# pulser.net
KiCad netlist of a schematic drawn in Altium Designer
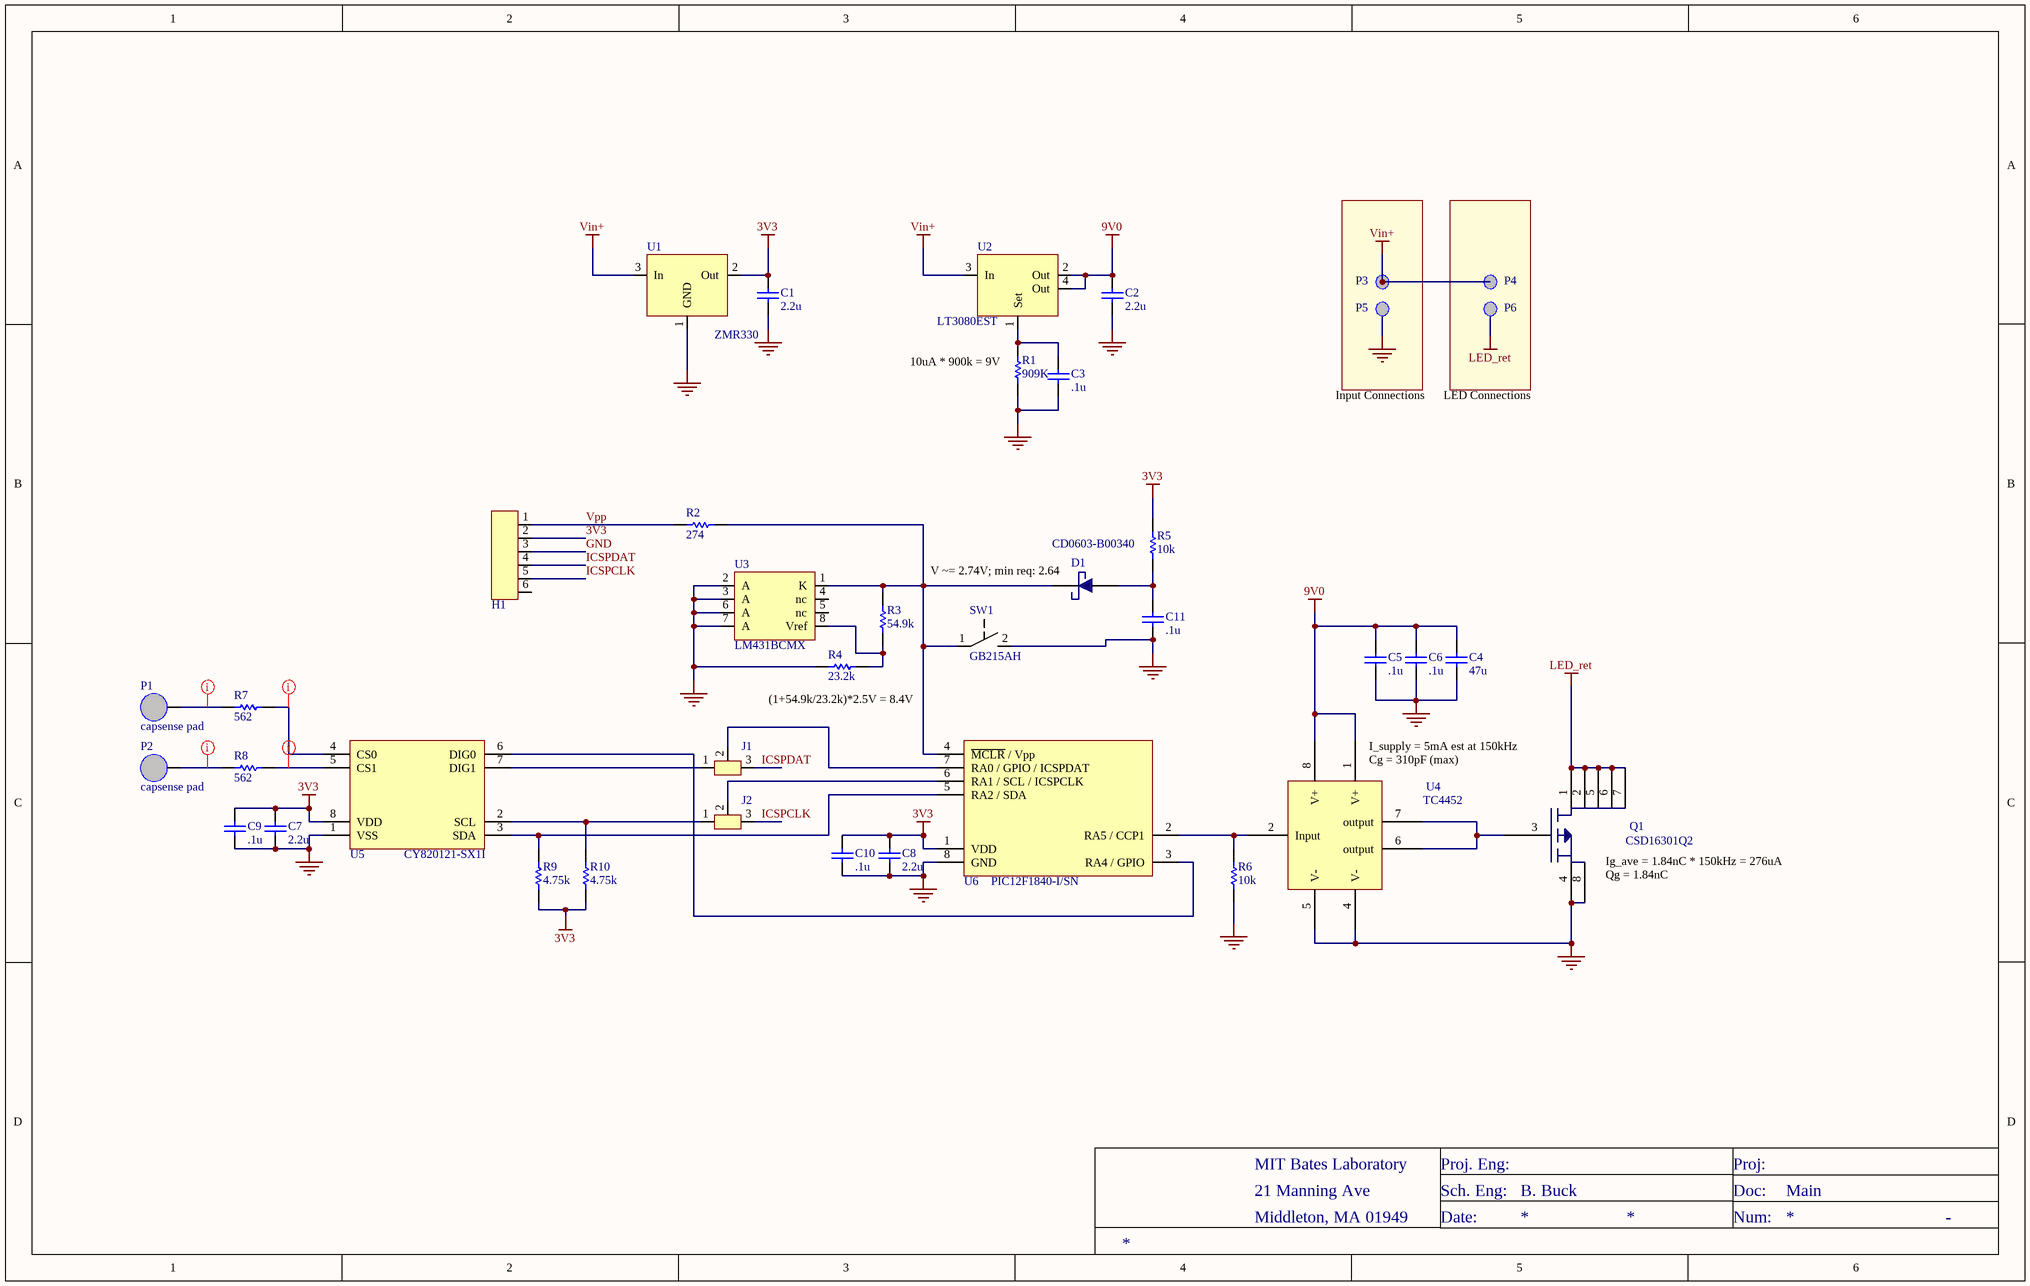
[diagram p0: pulser.SchDoc]

(export (version "E")
  (design (tool "Eeschema 10.0.6"))
  (components
    (comp (ref "C1")
      (value "2.2u")
      (footprint "SMD1210")
      (description "Capacitor")
      (fields (field (name "PARTNUMBER") "C1210C225K5RAC") (field (name "MANUFACTURER") "Kemet"))
      (libsource (lib "pulser") (part "Cap"))
    )
    (comp (ref "C2")
      (value "2.2u")
      (footprint "SMD1210")
      (description "Capacitor")
      (fields (field (name "PARTNUMBER") "C1210C225K5RAC") (field (name "MANUFACTURER") "Kemet"))
      (libsource (lib "pulser") (part "Cap"))
    )
    (comp (ref "C3")
      (value ".1u")
      (footprint "SMD0603")
      (description "Capacitor")
      (fields
        (field (name "PARTNUMBER") "250R14W104KV4T")
        (field (name "MANUFACTURER") "Johanson Dielectrics")
      )
      (libsource (lib "pulser") (part "Cap"))
    )
    (comp (ref "C4")
      (value "47u")
      (footprint "SMD1812")
      (description "Capacitor")
      (fields (field (name "PARTNUMBER") "C1812C475K5RAC") (field (name "MANUFACTURER") "Kemet"))
      (libsource (lib "pulser") (part "Cap"))
    )
    (comp (ref "C5")
      (value ".1u")
      (footprint "SMD0603")
      (description "Capacitor")
      (fields
        (field (name "PARTNUMBER") "250R14W104KV4T")
        (field (name "MANUFACTURER") "Johanson Dielectrics")
      )
      (libsource (lib "pulser") (part "Cap"))
    )
    (comp (ref "C6")
      (value ".1u")
      (footprint "SMD0603")
      (description "Capacitor")
      (fields
        (field (name "PARTNUMBER") "250R14W104KV4T")
        (field (name "MANUFACTURER") "Johanson Dielectrics")
      )
      (libsource (lib "pulser") (part "Cap"))
    )
    (comp (ref "C7")
      (value "2.2u")
      (footprint "SMD1210")
      (description "Capacitor")
      (fields (field (name "PARTNUMBER") "C1210C225K5RAC") (field (name "MANUFACTURER") "Kemet"))
      (libsource (lib "pulser") (part "Cap"))
    )
    (comp (ref "C8")
      (value "2.2u")
      (footprint "SMD1210")
      (description "Capacitor")
      (fields (field (name "PARTNUMBER") "C1210C225K5RAC") (field (name "MANUFACTURER") "Kemet"))
      (libsource (lib "pulser") (part "Cap"))
    )
    (comp (ref "C9")
      (value ".1u")
      (footprint "SMD0603")
      (description "Capacitor")
      (fields
        (field (name "PARTNUMBER") "250R14W104KV4T")
        (field (name "MANUFACTURER") "Johanson Dielectrics")
      )
      (libsource (lib "pulser") (part "Cap"))
    )
    (comp (ref "C10")
      (value ".1u")
      (footprint "SMD0603")
      (description "Capacitor")
      (fields
        (field (name "PARTNUMBER") "250R14W104KV4T")
        (field (name "MANUFACTURER") "Johanson Dielectrics")
      )
      (libsource (lib "pulser") (part "Cap"))
    )
    (comp (ref "C11")
      (value ".1u")
      (footprint "SMD0603")
      (description "Capacitor")
      (fields
        (field (name "PARTNUMBER") "250R14W104KV4T")
        (field (name "MANUFACTURER") "Johanson Dielectrics")
      )
      (libsource (lib "pulser") (part "Cap"))
    )
    (comp (ref "D1")
      (value "CD0603-B00340")
      (footprint "SMD0603 Polarized")
      (description "Schottky Diode")
      (fields (field (name "MANUFACTURER") "Bourns"))
      (libsource (lib "pulser") (part "CD0603-B00340"))
    )
    (comp (ref "H1")
      (value "6 pin header")
      (footprint "6 pin header")
      (description "6 Pin Header")
      (libsource (lib "pulser") (part "6 pin header"))
    )
    (comp (ref "J1")
      (value "jumper")
      (footprint "3 PIN HEADER")
      (description "Three Pin Jumper")
      (libsource (lib "pulser") (part "jumper"))
    )
    (comp (ref "J2")
      (value "jumper")
      (footprint "3 PIN HEADER")
      (description "Three Pin Jumper")
      (libsource (lib "pulser") (part "jumper"))
    )
    (comp (ref "P1")
      (value "capsense pad")
      (footprint "capsense 1cm")
      (description "circular capsense pad")
      (libsource (lib "pulser") (part "capsense pad 1"))
    )
    (comp (ref "P2")
      (value "capsense pad")
      (footprint "capsense 1cm")
      (description "circular capsense pad")
      (libsource (lib "pulser") (part "capsense pad 1"))
    )
    (comp (ref "P3")
      (value "16AWG Solder Point")
      (footprint "16 AWG Solder Point")
      (libsource (lib "pulser") (part "16AWG Solder Point"))
    )
    (comp (ref "P4")
      (value "16AWG Solder Point")
      (footprint "16 AWG Solder Point")
      (libsource (lib "pulser") (part "16AWG Solder Point"))
    )
    (comp (ref "P5")
      (value "16AWG Solder Point")
      (footprint "16 AWG Solder Point")
      (libsource (lib "pulser") (part "16AWG Solder Point"))
    )
    (comp (ref "P6")
      (value "16AWG Solder Point")
      (footprint "16 AWG Solder Point")
      (libsource (lib "pulser") (part "16AWG Solder Point"))
    )
    (comp (ref "Q1")
      (value "CSD16301Q2")
      (footprint "CSD16301Q2")
      (description "N Ch. MOSFET")
      (fields (field (name "MANUFACTURER") "Texas Instruments"))
      (libsource (lib "pulser") (part "CSD16301Q2"))
    )
    (comp (ref "R1")
      (value "909K")
      (footprint "SMD0603")
      (description "Resistor")
      (fields (field (name "PARTNUMBER") "CRCW0603909KFK") (field (name "MANUFACTURER") "Vishay / Dale"))
      (libsource (lib "pulser") (part "Res"))
    )
    (comp (ref "R2")
      (value "274")
      (footprint "SMD0603")
      (description "Resistor")
      (fields (field (name "PARTNUMBER") "CRCW0603274RFK") (field (name "MANUFACTURER") "Vishay / Dale"))
      (libsource (lib "pulser") (part "Res"))
    )
    (comp (ref "R3")
      (value "54.9k")
      (footprint "SMD0603")
      (description "Resistor")
      (fields (field (name "PARTNUMBER") "CRCW060354K9FK") (field (name "MANUFACTURER") "Vishay / Dale"))
      (libsource (lib "pulser") (part "Res"))
    )
    (comp (ref "R4")
      (value "23.2k")
      (footprint "SMD0603")
      (description "Resistor")
      (fields (field (name "PARTNUMBER") "CRCW060323K2FK") (field (name "MANUFACTURER") "Vishay / Dale"))
      (libsource (lib "pulser") (part "Res"))
    )
    (comp (ref "R5")
      (value "10k")
      (footprint "SMD0603")
      (description "Resistor")
      (fields (field (name "PARTNUMBER") "CRCW060310K0FK") (field (name "MANUFACTURER") "Vishay / Dale"))
      (libsource (lib "pulser") (part "Res"))
    )
    (comp (ref "R6")
      (value "10k")
      (footprint "SMD0603")
      (description "Resistor")
      (fields (field (name "PARTNUMBER") "CRCW060310K0FK") (field (name "MANUFACTURER") "Vishay / Dale"))
      (libsource (lib "pulser") (part "Res"))
    )
    (comp (ref "R7")
      (value "562")
      (footprint "SMD0603")
      (description "Resistor")
      (fields (field (name "PARTNUMBER") "CRCW0603562RFK") (field (name "MANUFACTURER") "Vishay / Dale"))
      (libsource (lib "pulser") (part "Res"))
    )
    (comp (ref "R8")
      (value "562")
      (footprint "SMD0603")
      (description "Resistor")
      (fields (field (name "PARTNUMBER") "CRCW0603562RFK") (field (name "MANUFACTURER") "Vishay / Dale"))
      (libsource (lib "pulser") (part "Res"))
    )
    (comp (ref "R9")
      (value "4.75k")
      (footprint "SMD0603")
      (description "Resistor")
      (fields (field (name "PARTNUMBER") "CRCW06034K75FK") (field (name "MANUFACTURER") "Vishay / Dale"))
      (libsource (lib "pulser") (part "Res"))
    )
    (comp (ref "R10")
      (value "4.75k")
      (footprint "SMD0603")
      (description "Resistor")
      (fields (field (name "PARTNUMBER") "CRCW06034K75FK") (field (name "MANUFACTURER") "Vishay / Dale"))
      (libsource (lib "pulser") (part "Res"))
    )
    (comp (ref "SW1")
      (value "GB215AH")
      (footprint "GB215AH")
      (description "SPST Normally Open Switch")
      (fields (field (name "PARTNUMBER") "GB125AH") (field (name "MANUFACTURER") "NKK Switches"))
      (libsource (lib "pulser") (part "GB215AH"))
    )
    (comp (ref "U1")
      (value "ZMR330")
      (footprint "SOT23 - Diodes")
      (description "Diodes 3.3V LDO regulator, 50mA")
      (fields (field (name "MANUFACTURER") "Diodes") (field (name "PARTNUMBER") "ZMR330FTA"))
      (libsource (lib "pulser") (part "ZMR330"))
    )
    (comp (ref "U2")
      (value "LT3080EST")
      (footprint "SOT233")
      (description "Adjustable Regulator, SOT-223 Package")
      (fields (field (name "MANUFACTURER") "Linear Technologies"))
      (libsource (lib "pulser") (part "LT3080EST"))
    )
    (comp (ref "U3")
      (value "LM431BCMX")
      (footprint "8 PIN SOIC")
      (description "Adjustable Voltage Reference")
      (fields (field (name "MANUFACTURER") "Fairchild Semiconductor") (field (name "PARTNUMBER") "LM431ACMX"))
      (libsource (lib "pulser") (part "LM431BCMX"))
    )
    (comp (ref "U4")
      (value "TC4452")
      (footprint "8 PIN SOIC")
      (description "MOSFET Gate Driver, Low Side, Non Inverting 13A max")
      (fields (field (name "MANUFACTURER") "Microchip") (field (name "PARTNUMBER") "TC4452VOA"))
      (libsource (lib "pulser") (part "TC4452"))
    )
    (comp (ref "U5")
      (value "CY820121-SX1I")
      (footprint "8 PIN SOIC")
      (description "Capsense Module, 2 button")
      (fields (field (name "PARTNUMBER") "CY8C20121-SX1IX") (field (name "MANUFACTURER") "Cypress"))
      (libsource (lib "pulser") (part "CY820121-SX1I"))
    )
    (comp (ref "U6")
      (value "PIC12F1840-I/SN")
      (footprint "8 PIN SOIC")
      (description "8 Bit RISC uController")
      (fields (field (name "MANUFACTURER") "Microchip"))
      (libsource (lib "pulser") (part "PIC12F1840-I/SN"))
    )
  )
  (nets
    (net (code "1") (name "/ICSPCLK") (class "Default")
      (node (ref "H1") (pin "5") (pinfunction "5_5") (pintype "passive"))
      (node (ref "J2") (pin "3") (pinfunction "3_3") (pintype "passive"))
    )
    (net (code "2") (name "/ICSPDAT") (class "Default")
      (node (ref "H1") (pin "4") (pinfunction "4_4") (pintype "passive"))
      (node (ref "J1") (pin "3") (pinfunction "3_3") (pintype "passive"))
    )
    (net (code "3") (name "/Vpp") (class "Default")
      (node (ref "H1") (pin "1") (pinfunction "1_1") (pintype "passive"))
      (node (ref "R2") (pin "2") (pinfunction "2_2") (pintype "passive"))
    )
    (net (code "4") (name "3V3") (class "Default")
      (node (ref "C1") (pin "2") (pinfunction "2_2") (pintype "passive"))
      (node (ref "C10") (pin "2") (pinfunction "2_2") (pintype "passive"))
      (node (ref "C7") (pin "2") (pinfunction "2_2") (pintype "passive"))
      (node (ref "C8") (pin "2") (pinfunction "2_2") (pintype "passive"))
      (node (ref "C9") (pin "2") (pinfunction "2_2") (pintype "passive"))
      (node (ref "H1") (pin "2") (pinfunction "2_2") (pintype "passive"))
      (node (ref "R10") (pin "2") (pinfunction "2_2") (pintype "passive"))
      (node (ref "R5") (pin "1") (pinfunction "1_1") (pintype "passive"))
      (node (ref "R9") (pin "2") (pinfunction "2_2") (pintype "passive"))
      (node (ref "U1") (pin "2") (pinfunction "Out_2") (pintype "passive"))
      (node (ref "U5") (pin "8") (pinfunction "VDD_8") (pintype "passive"))
      (node (ref "U6") (pin "1") (pinfunction "VDD_1") (pintype "passive"))
    )
    (net (code "5") (name "9V0") (class "Default")
      (node (ref "C2") (pin "2") (pinfunction "2_2") (pintype "passive"))
      (node (ref "C4") (pin "2") (pinfunction "2_2") (pintype "passive"))
      (node (ref "C5") (pin "2") (pinfunction "2_2") (pintype "passive"))
      (node (ref "C6") (pin "2") (pinfunction "2_2") (pintype "passive"))
      (node (ref "U2") (pin "2") (pinfunction "Out_2") (pintype "passive"))
      (node (ref "U2") (pin "4") (pinfunction "Out_4") (pintype "passive"))
      (node (ref "U4") (pin "1") (pinfunction "V+_1") (pintype "passive"))
      (node (ref "U4") (pin "8") (pinfunction "V+_8") (pintype "passive"))
    )
    (net (code "6") (name "GND") (class "Default")
      (node (ref "C1") (pin "1") (pinfunction "1_1") (pintype "passive"))
      (node (ref "C10") (pin "1") (pinfunction "1_1") (pintype "passive"))
      (node (ref "C11") (pin "1") (pinfunction "1_1") (pintype "passive"))
      (node (ref "C2") (pin "1") (pinfunction "1_1") (pintype "passive"))
      (node (ref "C3") (pin "1") (pinfunction "1_1") (pintype "passive"))
      (node (ref "C4") (pin "1") (pinfunction "1_1") (pintype "passive"))
      (node (ref "C5") (pin "1") (pinfunction "1_1") (pintype "passive"))
      (node (ref "C6") (pin "1") (pinfunction "1_1") (pintype "passive"))
      (node (ref "C7") (pin "1") (pinfunction "1_1") (pintype "passive"))
      (node (ref "C8") (pin "1") (pinfunction "1_1") (pintype "passive"))
      (node (ref "C9") (pin "1") (pinfunction "1_1") (pintype "passive"))
      (node (ref "H1") (pin "3") (pinfunction "3_3") (pintype "passive"))
      (node (ref "P5") (pin "1") (pinfunction "1_1") (pintype "passive"))
      (node (ref "Q1") (pin "4") (pintype "passive"))
      (node (ref "Q1") (pin "8") (pintype "passive"))
      (node (ref "R1") (pin "1") (pinfunction "1_1") (pintype "passive"))
      (node (ref "R4") (pin "2") (pinfunction "2_2") (pintype "passive"))
      (node (ref "R6") (pin "2") (pinfunction "2_2") (pintype "passive"))
      (node (ref "SW1") (pin "2") (pinfunction "2_2") (pintype "passive"))
      (node (ref "U1") (pin "1") (pinfunction "GND_1") (pintype "passive"))
      (node (ref "U3") (pin "2") (pinfunction "A_2") (pintype "passive"))
      (node (ref "U3") (pin "3") (pinfunction "A_3") (pintype "passive"))
      (node (ref "U3") (pin "6") (pinfunction "A_6") (pintype "passive"))
      (node (ref "U3") (pin "7") (pinfunction "A_7") (pintype "passive"))
      (node (ref "U4") (pin "4") (pinfunction "V-_4") (pintype "passive"))
      (node (ref "U4") (pin "5") (pinfunction "V-_5") (pintype "passive"))
      (node (ref "U5") (pin "1") (pinfunction "VSS_1") (pintype "passive"))
      (node (ref "U6") (pin "8") (pinfunction "GND_8") (pintype "passive"))
    )
    (net (code "7") (name "LED_ret") (class "Default")
      (node (ref "P6") (pin "1") (pinfunction "1_1") (pintype "passive"))
      (node (ref "Q1") (pin "1") (pintype "passive"))
      (node (ref "Q1") (pin "2") (pintype "passive"))
      (node (ref "Q1") (pin "5") (pintype "passive"))
      (node (ref "Q1") (pin "6") (pintype "passive"))
      (node (ref "Q1") (pin "7") (pintype "passive"))
    )
    (net (code "8") (name "Net-(D1-A)") (class "Default")
      (node (ref "C11") (pin "2") (pinfunction "2_2") (pintype "passive"))
      (node (ref "D1") (pin "2") (pinfunction "A_2") (pintype "passive"))
      (node (ref "R5") (pin "2") (pinfunction "2_2") (pintype "passive"))
    )
    (net (code "9") (name "Net-(D1-K)") (class "Default")
      (node (ref "D1") (pin "1") (pinfunction "K_1") (pintype "passive"))
      (node (ref "R2") (pin "1") (pinfunction "1_1") (pintype "passive"))
      (node (ref "R3") (pin "2") (pinfunction "2_2") (pintype "passive"))
      (node (ref "SW1") (pin "1") (pinfunction "1_1") (pintype "passive"))
      (node (ref "U3") (pin "1") (pinfunction "K_1") (pintype "passive"))
      (node (ref "U6") (pin "4") (pinfunction "~{MCLR}_/_Vpp_4") (pintype "passive"))
    )
    (net (code "10") (name "Net-(P1-Pad1)") (class "Default")
      (node (ref "P1") (pin "1") (pintype "passive"))
      (node (ref "R7") (pin "2") (pinfunction "2_2") (pintype "passive"))
    )
    (net (code "11") (name "Net-(P2-Pad1)") (class "Default")
      (node (ref "P2") (pin "1") (pintype "passive"))
      (node (ref "R8") (pin "2") (pinfunction "2_2") (pintype "passive"))
    )
    (net (code "12") (name "Net-(Q1-Pad3)") (class "Default")
      (node (ref "Q1") (pin "3") (pintype "passive"))
      (node (ref "U4") (pin "6") (pinfunction "output_6") (pintype "passive"))
      (node (ref "U4") (pin "7") (pinfunction "output_7") (pintype "passive"))
    )
    (net (code "13") (name "Net-(U2-Set)") (class "Default")
      (node (ref "C3") (pin "2") (pinfunction "2_2") (pintype "passive"))
      (node (ref "R1") (pin "2") (pinfunction "2_2") (pintype "passive"))
      (node (ref "U2") (pin "1") (pinfunction "Set_1") (pintype "passive"))
    )
    (net (code "14") (name "Net-(U3-Vref)") (class "Default")
      (node (ref "R3") (pin "1") (pinfunction "1_1") (pintype "passive"))
      (node (ref "R4") (pin "1") (pinfunction "1_1") (pintype "passive"))
      (node (ref "U3") (pin "8") (pinfunction "Vref_8") (pintype "passive"))
    )
    (net (code "15") (name "Net-(U4-Input)") (class "Default")
      (node (ref "R6") (pin "1") (pinfunction "1_1") (pintype "passive"))
      (node (ref "U4") (pin "2") (pinfunction "Input_2") (pintype "passive"))
      (node (ref "U6") (pin "2") (pinfunction "RA5_/_CCP1_2") (pintype "passive"))
    )
    (net (code "16") (name "Net-(U5-CS0)") (class "Default")
      (node (ref "R7") (pin "1") (pinfunction "1_1") (pintype "passive"))
      (node (ref "U5") (pin "4") (pinfunction "CS0_4") (pintype "passive"))
    )
    (net (code "17") (name "Net-(U5-CS1)") (class "Default")
      (node (ref "R8") (pin "1") (pinfunction "1_1") (pintype "passive"))
      (node (ref "U5") (pin "5") (pinfunction "CS1_5") (pintype "passive"))
    )
    (net (code "18") (name "Net-(U5-DIG0)") (class "Default")
      (node (ref "U5") (pin "6") (pinfunction "DIG0_6") (pintype "passive"))
      (node (ref "U6") (pin "3") (pinfunction "RA4_/_GPIO_3") (pintype "passive"))
    )
    (net (code "19") (name "Net-(U5-DIG1)") (class "Default")
      (node (ref "J1") (pin "1") (pinfunction "1_1") (pintype "passive"))
      (node (ref "U5") (pin "7") (pinfunction "DIG1_7") (pintype "passive"))
    )
    (net (code "20") (name "Net-(U5-SCL)") (class "Default")
      (node (ref "J2") (pin "1") (pinfunction "1_1") (pintype "passive"))
      (node (ref "R10") (pin "1") (pinfunction "1_1") (pintype "passive"))
      (node (ref "U5") (pin "2") (pinfunction "SCL_2") (pintype "passive"))
    )
    (net (code "21") (name "Net-(U5-SDA)") (class "Default")
      (node (ref "R9") (pin "1") (pinfunction "1_1") (pintype "passive"))
      (node (ref "U5") (pin "3") (pinfunction "SDA_3") (pintype "passive"))
      (node (ref "U6") (pin "5") (pinfunction "RA2_/_SDA_5") (pintype "passive"))
    )
    (net (code "22") (name "Net-(U6-RA0_{slash}_GPIO_{slash}_ICSPDAT)") (class "Default")
      (node (ref "J1") (pin "2") (pinfunction "2_2") (pintype "passive"))
      (node (ref "U6") (pin "7") (pinfunction "RA0_/_GPIO_/_ICSPDAT_7") (pintype "passive"))
    )
    (net (code "23") (name "Net-(U6-RA1_{slash}_SCL_{slash}_ICSPCLK)") (class "Default")
      (node (ref "J2") (pin "2") (pinfunction "2_2") (pintype "passive"))
      (node (ref "U6") (pin "6") (pinfunction "RA1_/_SCL_/_ICSPCLK_6") (pintype "passive"))
    )
    (net (code "24") (name "Vin+") (class "Default")
      (node (ref "P3") (pin "1") (pinfunction "1_1") (pintype "passive"))
      (node (ref "P4") (pin "1") (pinfunction "1_1") (pintype "passive"))
      (node (ref "U1") (pin "3") (pinfunction "In_3") (pintype "passive"))
      (node (ref "U2") (pin "3") (pinfunction "In_3") (pintype "passive"))
    )
    (net (code "25") (name "unconnected-(H1-Pad6)") (class "Default")
      (node (ref "H1") (pin "6") (pinfunction "6_6") (pintype "passive"))
    )
    (net (code "26") (name "unconnected-(U3-nc-Pad4)") (class "Default")
      (node (ref "U3") (pin "4") (pinfunction "nc_4") (pintype "passive"))
    )
    (net (code "27") (name "unconnected-(U3-nc-Pad5)") (class "Default")
      (node (ref "U3") (pin "5") (pinfunction "nc_5") (pintype "passive"))
    )
  )
)
